# RFR24_AMS_Design_-_Top_Level_V1.net
KiCad netlist of a schematic drawn in Altium Designer
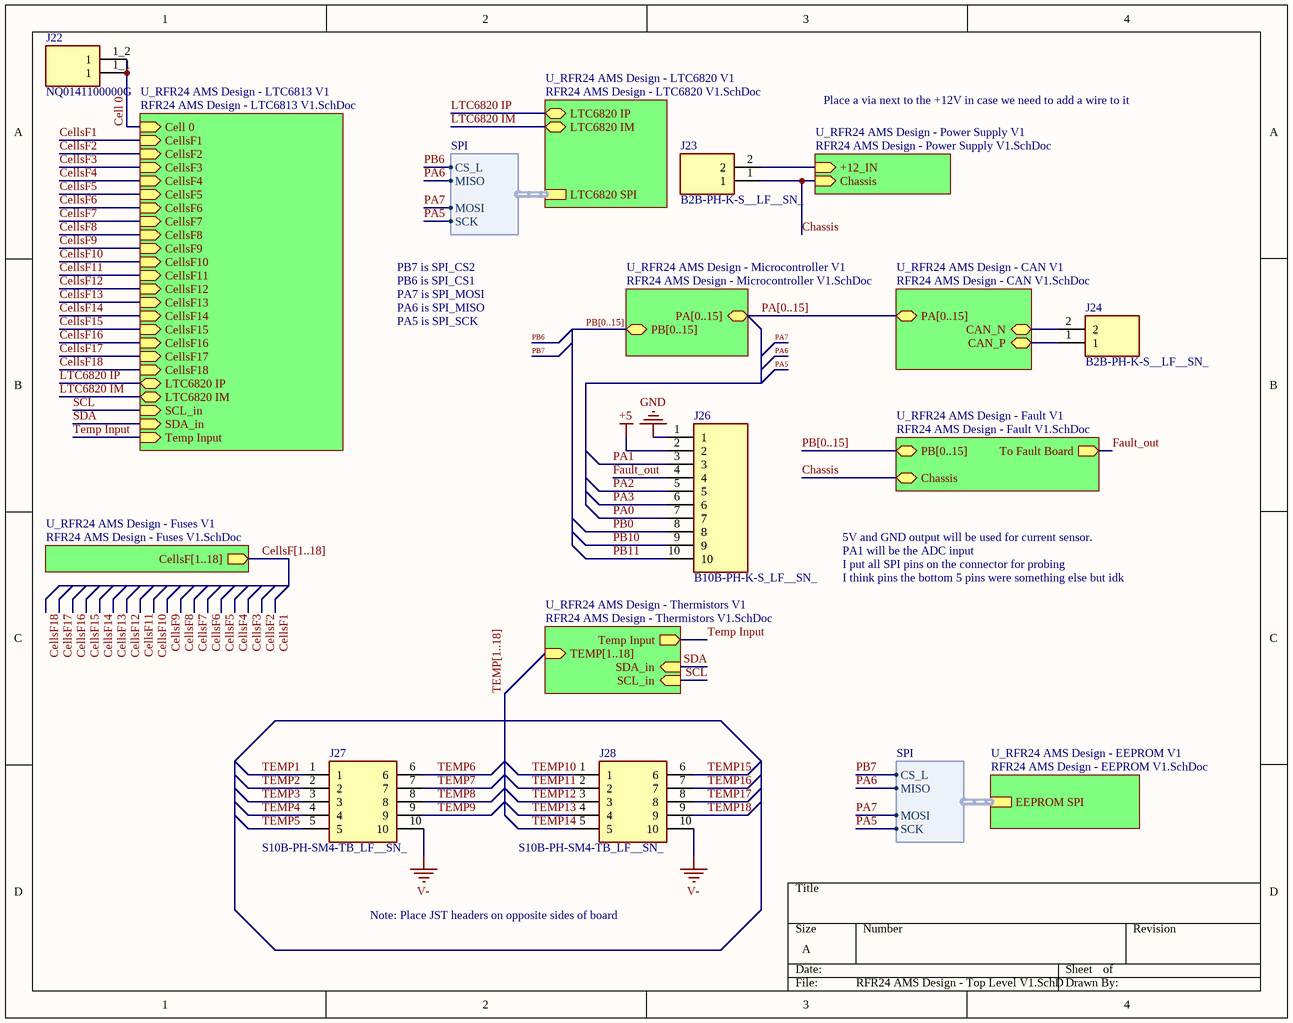
[diagram p0: RFR24 AMS Design - Top Level V1.SchDoc]

(export (version "E")
  (design (tool "Eeschema 10.0.6"))
  (components
    (comp (ref "J22")
      (value "NQ0141100000G")
      (footprint "AMPHENOL_NQ0141100000G")
      (description "1 Position Wire to Board Terminal Block Horizontal with Board Surface Mount")
      (fields (field (name "MF") "Amphenol Anytek"))
      (libsource (lib "NQ0141100000G") (part "NQ0141100000G"))
    )
    (comp (ref "J23")
      (value "B2B-PH-K-S__LF__SN_")
      (footprint "SamacSys:B2BPHKSLFSN")
      (description "Circulator or Directional Coupler")
      (fields (field (name "MANUFACTURER_PART_NUMBER") "B2B-PH-K-S (LF)(SN)"))
      (libsource (lib "*") (part "B2B-PH-K-S__LF__SN_"))
    )
    (comp (ref "J24")
      (value "B2B-PH-K-S__LF__SN_")
      (footprint "SamacSys:B2BPHKSLFSN")
      (description "Circulator or Directional Coupler")
      (fields (field (name "MANUFACTURER_PART_NUMBER") "B2B-PH-K-S (LF)(SN)"))
      (libsource (lib "") (part "B2B-PH-K-S__LF__SN__1"))
    )
    (comp (ref "J26")
      (value "B10B-PH-K-S_LF__SN_")
      (footprint "SamacSys:SHDR10W50P0X200_1X10_2190X450X600P")
      (description "Connector")
      (fields (field (name "MANUFACTURER_PART_NUMBER") "B10B-PH-K-S(LF)(SN)"))
      (libsource (lib "*") (part "B10B-PH-K-S_LF__SN_"))
    )
    (comp (ref "J27")
      (value "S10B-PH-SM4-TB_LF__SN_")
      (footprint "SamacSys:S10B-PH-SM4-TB")
      (description "Connector")
      (fields (field (name "MANUFACTURER_PART_NUMBER") "S10B-PH-SM4-TB(LF)(SN)"))
      (libsource (lib "*") (part "S10B-PH-SM4-TB_LF__SN_"))
    )
    (comp (ref "J28")
      (value "S10B-PH-SM4-TB_LF__SN_")
      (footprint "SamacSys:S10B-PH-SM4-TB")
      (description "Connector")
      (fields (field (name "MANUFACTURER_PART_NUMBER") "S10B-PH-SM4-TB(LF)(SN)"))
      (libsource (lib "*") (part "S10B-PH-SM4-TB_LF__SN_"))
    )
  )
  (nets
    (net (code "22") (name "+5") (class "Default")
      (node (ref "J26") (pin "2") (pinfunction "2_2") (pintype "passive"))
    )
    (net (code "23") (name "/+12_IN") (class "Default")
      (node (ref "J23") (pin "2") (pinfunction "2_2") (pintype "passive"))
    )
    (net (code "24") (name "/CAN_N") (class "Default")
      (node (ref "J24") (pin "2") (pinfunction "2_2") (pintype "passive"))
    )
    (net (code "25") (name "/CAN_P") (class "Default")
      (node (ref "J24") (pin "1") (pinfunction "1_1") (pintype "passive"))
    )
    (net (code "26") (name "/Cell 0") (class "Default")
      (node (ref "J22") (pin "1_1") (pinfunction "1_1_1") (pintype "passive"))
      (node (ref "J22") (pin "1_2") (pinfunction "1_1_2") (pintype "passive"))
    )
    (net (code "46") (name "/Chassis") (class "Default")
      (node (ref "J23") (pin "1") (pinfunction "1_1") (pintype "passive"))
    )
    (net (code "47") (name "/Fault_out") (class "Default")
      (node (ref "J26") (pin "4") (pinfunction "4_4") (pintype "passive"))
    )
    (net (code "50") (name "/PA0") (class "Default")
      (node (ref "J26") (pin "7") (pinfunction "7_7") (pintype "passive"))
    )
    (net (code "51") (name "/PA1") (class "Default")
      (node (ref "J26") (pin "3") (pinfunction "3_3") (pintype "passive"))
    )
    (net (code "52") (name "/PA2") (class "Default")
      (node (ref "J26") (pin "5") (pinfunction "5_5") (pintype "passive"))
    )
    (net (code "53") (name "/PA3") (class "Default")
      (node (ref "J26") (pin "6") (pinfunction "6_6") (pintype "passive"))
    )
    (net (code "58") (name "/PB0") (class "Default")
      (node (ref "J26") (pin "8") (pinfunction "8_8") (pintype "passive"))
    )
    (net (code "61") (name "/PB10") (class "Default")
      (node (ref "J26") (pin "9") (pinfunction "9_9") (pintype "passive"))
    )
    (net (code "62") (name "/PB11") (class "Default")
      (node (ref "J26") (pin "10") (pinfunction "10_10") (pintype "passive"))
    )
    (net (code "66") (name "/TEMP1") (class "Default")
      (node (ref "J27") (pin "1") (pinfunction "1_1") (pintype "passive"))
    )
    (net (code "67") (name "/TEMP2") (class "Default")
      (node (ref "J27") (pin "2") (pinfunction "2_2") (pintype "passive"))
    )
    (net (code "68") (name "/TEMP3") (class "Default")
      (node (ref "J27") (pin "3") (pinfunction "3_3") (pintype "passive"))
    )
    (net (code "69") (name "/TEMP4") (class "Default")
      (node (ref "J27") (pin "4") (pinfunction "4_4") (pintype "passive"))
    )
    (net (code "70") (name "/TEMP5") (class "Default")
      (node (ref "J27") (pin "5") (pinfunction "5_5") (pintype "passive"))
    )
    (net (code "71") (name "/TEMP6") (class "Default")
      (node (ref "J27") (pin "6") (pinfunction "6_6") (pintype "passive"))
    )
    (net (code "72") (name "/TEMP7") (class "Default")
      (node (ref "J27") (pin "7") (pinfunction "7_7") (pintype "passive"))
    )
    (net (code "73") (name "/TEMP8") (class "Default")
      (node (ref "J27") (pin "8") (pinfunction "8_8") (pintype "passive"))
    )
    (net (code "74") (name "/TEMP9") (class "Default")
      (node (ref "J27") (pin "9") (pinfunction "9_9") (pintype "passive"))
    )
    (net (code "75") (name "/TEMP10") (class "Default")
      (node (ref "J28") (pin "1") (pinfunction "1_1") (pintype "passive"))
    )
    (net (code "76") (name "/TEMP11") (class "Default")
      (node (ref "J28") (pin "2") (pinfunction "2_2") (pintype "passive"))
    )
    (net (code "77") (name "/TEMP12") (class "Default")
      (node (ref "J28") (pin "3") (pinfunction "3_3") (pintype "passive"))
    )
    (net (code "78") (name "/TEMP13") (class "Default")
      (node (ref "J28") (pin "4") (pinfunction "4_4") (pintype "passive"))
    )
    (net (code "79") (name "/TEMP14") (class "Default")
      (node (ref "J28") (pin "5") (pinfunction "5_5") (pintype "passive"))
    )
    (net (code "80") (name "/TEMP15") (class "Default")
      (node (ref "J28") (pin "6") (pinfunction "6_6") (pintype "passive"))
    )
    (net (code "81") (name "/TEMP16") (class "Default")
      (node (ref "J28") (pin "7") (pinfunction "7_7") (pintype "passive"))
    )
    (net (code "82") (name "/TEMP17") (class "Default")
      (node (ref "J28") (pin "8") (pinfunction "8_8") (pintype "passive"))
    )
    (net (code "83") (name "/TEMP18") (class "Default")
      (node (ref "J28") (pin "9") (pinfunction "9_9") (pintype "passive"))
    )
    (net (code "87") (name "GND") (class "Default")
      (node (ref "J26") (pin "1") (pinfunction "1_1") (pintype "passive"))
    )
    (net (code "88") (name "V-") (class "Default")
      (node (ref "J27") (pin "10") (pinfunction "10_10") (pintype "passive"))
      (node (ref "J28") (pin "10") (pinfunction "10_10") (pintype "passive"))
    )
  )
)
